# MI0283QT_v20.net
KiCad netlist of a schematic drawn in EAGLE
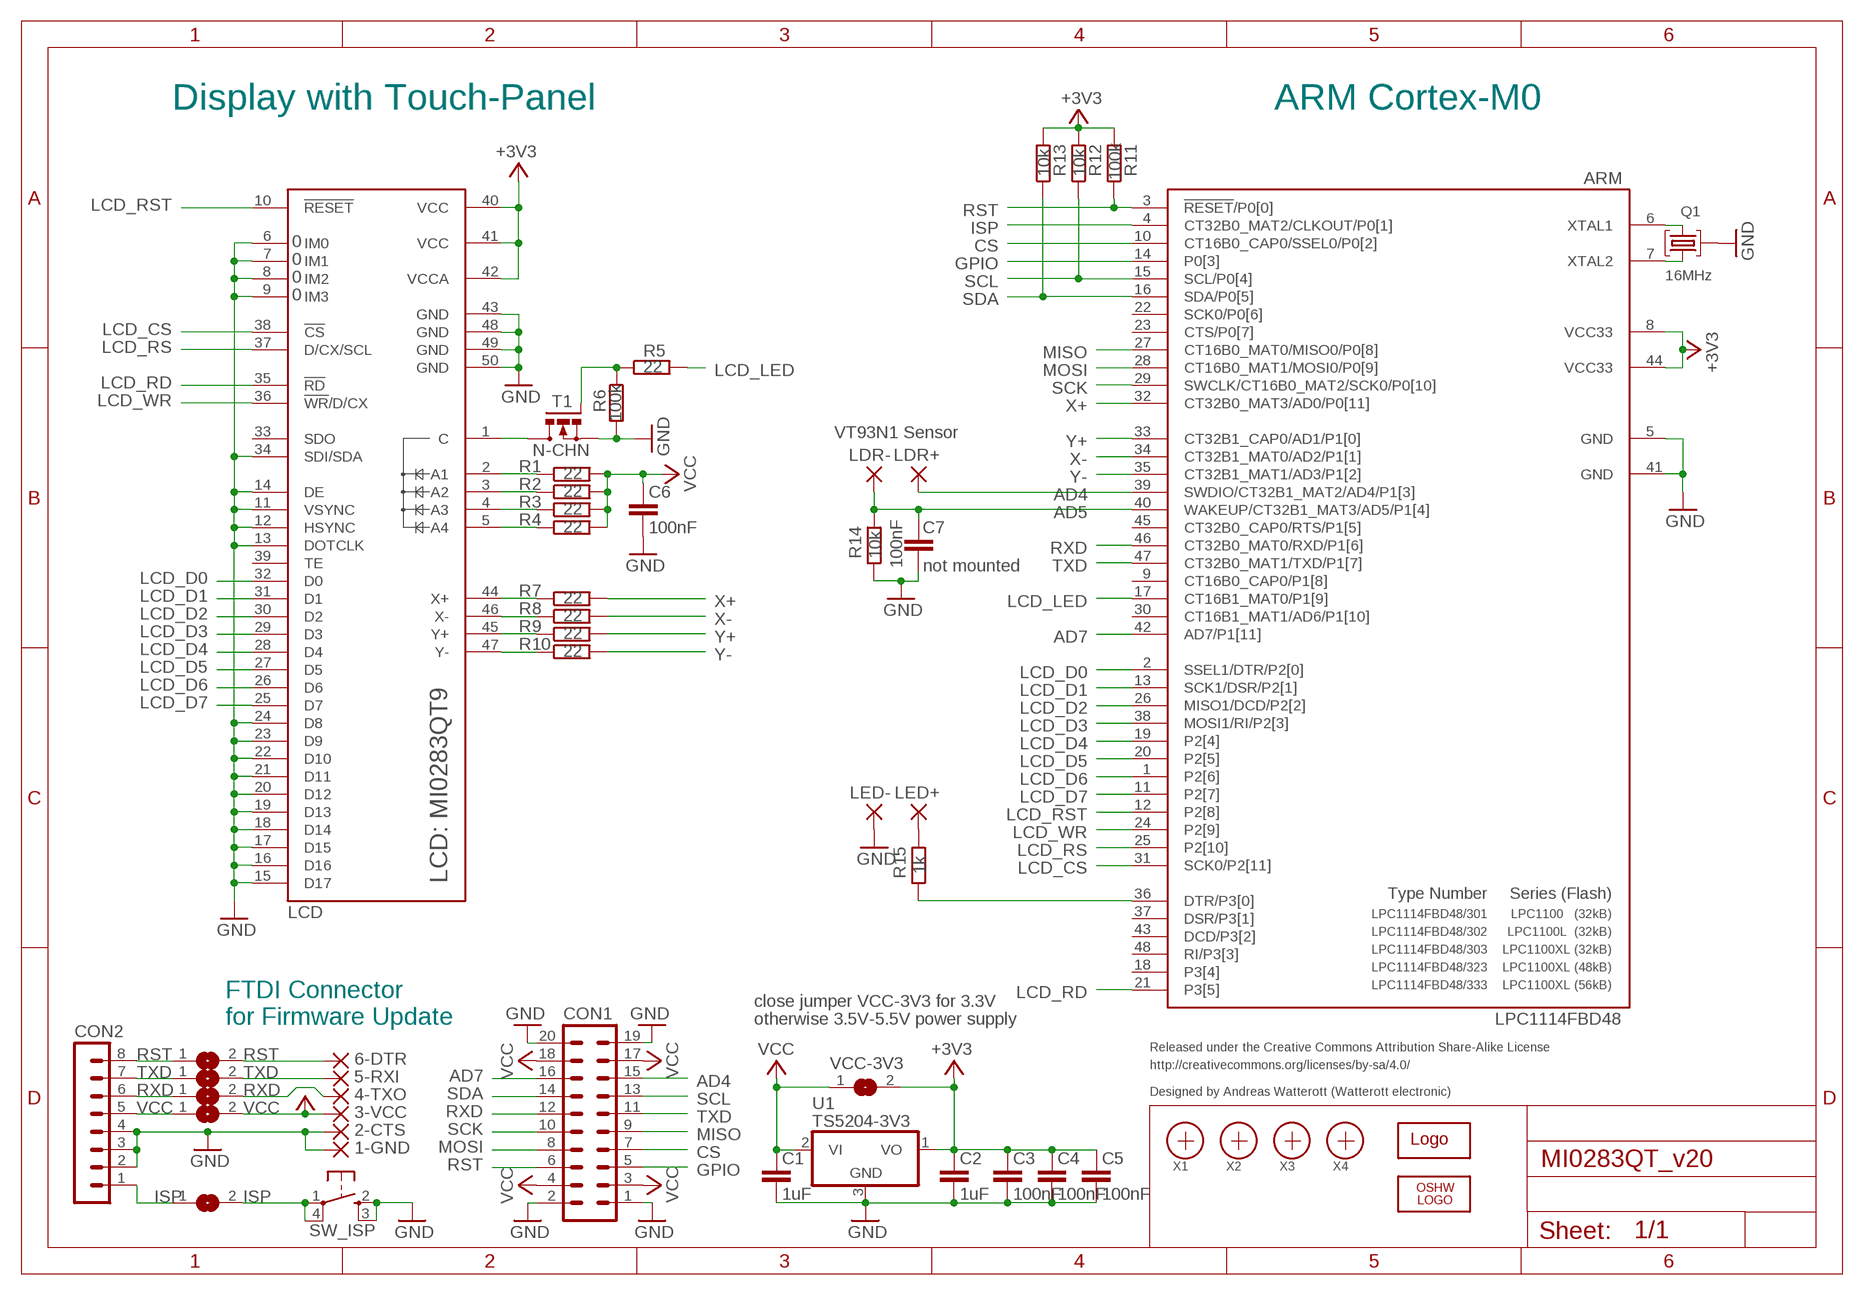
[diagram p0: schematic, sheet 1]

(export (version "E")
  (design (tool "Eeschema 10.0.6"))
  (components
    (comp (ref "1-GND")
      (value "WIREPADSMD1,27-254")
      (footprint "eagle-import:SMD1,27-2,54")
      (libsource (lib "eagle-import") (part "WIREPADSMD1,27-254"))
    )
    (comp (ref "2-CTS")
      (value "WIREPADSMD1,27-254")
      (footprint "eagle-import:SMD1,27-2,54")
      (libsource (lib "eagle-import") (part "WIREPADSMD1,27-254"))
    )
    (comp (ref "3-VCC")
      (value "WIREPADSMD1,27-254")
      (footprint "eagle-import:SMD1,27-2,54")
      (libsource (lib "eagle-import") (part "WIREPADSMD1,27-254"))
    )
    (comp (ref "4-TXO")
      (value "WIREPADSMD1,27-254")
      (footprint "eagle-import:SMD1,27-2,54")
      (libsource (lib "eagle-import") (part "WIREPADSMD1,27-254"))
    )
    (comp (ref "5-RXI")
      (value "WIREPADSMD1,27-254")
      (footprint "eagle-import:SMD1,27-2,54")
      (libsource (lib "eagle-import") (part "WIREPADSMD1,27-254"))
    )
    (comp (ref "6-DTR")
      (value "WIREPADSMD1,27-254")
      (footprint "eagle-import:SMD1,27-2,54")
      (libsource (lib "eagle-import") (part "WIREPADSMD1,27-254"))
    )
    (comp (ref "ARM")
      (value "LPC1114FBD48")
      (footprint "eagle-import:LQFP48")
      (libsource (lib "eagle-import") (part "LPC111X"))
    )
    (comp (ref "C1")
      (value "1uF")
      (footprint "eagle-import:C0603")
      (libsource (lib "eagle-import") (part "C-EUC0603"))
    )
    (comp (ref "C2")
      (value "1uF")
      (footprint "eagle-import:C0603")
      (libsource (lib "eagle-import") (part "C-EUC0603"))
    )
    (comp (ref "C3")
      (value "100nF")
      (footprint "eagle-import:C0603")
      (libsource (lib "eagle-import") (part "C-EUC0603"))
    )
    (comp (ref "C4")
      (value "100nF")
      (footprint "eagle-import:C0603")
      (libsource (lib "eagle-import") (part "C-EUC0603"))
    )
    (comp (ref "C5")
      (value "100nF")
      (footprint "eagle-import:C0603")
      (libsource (lib "eagle-import") (part "C-EUC0603"))
    )
    (comp (ref "C6")
      (value "100nF")
      (footprint "eagle-import:C0603")
      (libsource (lib "eagle-import") (part "C-EUC0603"))
    )
    (comp (ref "C7")
      (value "100nF")
      (footprint "eagle-import:C0603")
      (libsource (lib "eagle-import") (part "C-EUC0603"))
    )
    (comp (ref "CON1")
      (value "MA10-2")
      (footprint "eagle-import:MA10-2")
      (libsource (lib "eagle-import") (part "MA10-2"))
    )
    (comp (ref "CON2")
      (value "MA08-1")
      (footprint "eagle-import:MA08-1")
      (libsource (lib "eagle-import") (part "MA08-1"))
    )
    (comp (ref "ISP") (value "SJ") (footprint "eagle-import:SJ") (libsource (lib "eagle-import") (part "SJ")))
    (comp (ref "LCD")
      (value "MI0283QT9")
      (footprint "eagle-import:MI0283QT9")
      (libsource (lib "eagle-import") (part "MI0283QT9"))
    )
    (comp (ref "LDR+")
      (value "WIREPAD2,15/1,0")
      (footprint "eagle-import:2,15_1,0")
      (libsource (lib "eagle-import") (part "WIREPAD2,15/1,0"))
    )
    (comp (ref "LDR-")
      (value "WIREPAD2,15/1,0")
      (footprint "eagle-import:2,15_1,0")
      (libsource (lib "eagle-import") (part "WIREPAD2,15/1,0"))
    )
    (comp (ref "LED+")
      (value "WIREPAD2,15/1,0")
      (footprint "eagle-import:2,15_1,0")
      (libsource (lib "eagle-import") (part "WIREPAD2,15/1,0"))
    )
    (comp (ref "LED-")
      (value "WIREPAD2,15/1,0")
      (footprint "eagle-import:2,15_1,0")
      (libsource (lib "eagle-import") (part "WIREPAD2,15/1,0"))
    )
    (comp (ref "LOGO1")
      (value "OSHW_LOGO_6MILX0150-NT")
      (footprint "eagle-import:OSHW_6X150_NOTEXT")
      (libsource (lib "eagle-import") (part "OSHW_LOGO_6MILX0150-NT"))
    )
    (comp (ref "Q1")
      (value "16MHz")
      (footprint "eagle-import:SMD_OSC_35X15")
      (libsource (lib "eagle-import") (part "SMD_OSC2"))
    )
    (comp (ref "R1")
      (value "22")
      (footprint "eagle-import:R0603")
      (libsource (lib "eagle-import") (part "R-EU_R0603"))
    )
    (comp (ref "R2")
      (value "22")
      (footprint "eagle-import:R0603")
      (libsource (lib "eagle-import") (part "R-EU_R0603"))
    )
    (comp (ref "R3")
      (value "22")
      (footprint "eagle-import:R0603")
      (libsource (lib "eagle-import") (part "R-EU_R0603"))
    )
    (comp (ref "R4")
      (value "22")
      (footprint "eagle-import:R0603")
      (libsource (lib "eagle-import") (part "R-EU_R0603"))
    )
    (comp (ref "R5")
      (value "22")
      (footprint "eagle-import:R0603")
      (libsource (lib "eagle-import") (part "R-EU_R0603"))
    )
    (comp (ref "R6")
      (value "100k")
      (footprint "eagle-import:R0603")
      (libsource (lib "eagle-import") (part "R-EU_R0603"))
    )
    (comp (ref "R7")
      (value "22")
      (footprint "eagle-import:R0603")
      (libsource (lib "eagle-import") (part "R-EU_R0603"))
    )
    (comp (ref "R8")
      (value "22")
      (footprint "eagle-import:R0603")
      (libsource (lib "eagle-import") (part "R-EU_R0603"))
    )
    (comp (ref "R9")
      (value "22")
      (footprint "eagle-import:R0603")
      (libsource (lib "eagle-import") (part "R-EU_R0603"))
    )
    (comp (ref "R10")
      (value "22")
      (footprint "eagle-import:R0603")
      (libsource (lib "eagle-import") (part "R-EU_R0603"))
    )
    (comp (ref "R11")
      (value "100k")
      (footprint "eagle-import:R0603")
      (libsource (lib "eagle-import") (part "R-EU_R0603"))
    )
    (comp (ref "R12")
      (value "10k")
      (footprint "eagle-import:R0603")
      (libsource (lib "eagle-import") (part "R-EU_R0603"))
    )
    (comp (ref "R13")
      (value "10k")
      (footprint "eagle-import:R0603")
      (libsource (lib "eagle-import") (part "R-EU_R0603"))
    )
    (comp (ref "R14")
      (value "10k")
      (footprint "eagle-import:R0603")
      (libsource (lib "eagle-import") (part "R-EU_R0603"))
    )
    (comp (ref "R15")
      (value "1k")
      (footprint "eagle-import:R0603")
      (libsource (lib "eagle-import") (part "R-EU_R0603"))
    )
    (comp (ref "RST") (value "SJ") (footprint "eagle-import:SJ") (libsource (lib "eagle-import") (part "SJ")))
    (comp (ref "RXD") (value "SJ") (footprint "eagle-import:SJ") (libsource (lib "eagle-import") (part "SJ")))
    (comp (ref "SW_ISP")
      (value "SW_SMDS")
      (footprint "eagle-import:SW_SMD4@1")
      (libsource (lib "eagle-import") (part "SW_SMDS"))
    )
    (comp (ref "T1")
      (value "N-CHN")
      (footprint "eagle-import:MICRO3")
      (libsource (lib "eagle-import") (part "IRLML2502"))
    )
    (comp (ref "TXD") (value "SJ") (footprint "eagle-import:SJ") (libsource (lib "eagle-import") (part "SJ")))
    (comp (ref "U$1")
      (value "WE-LOGO")
      (footprint "eagle-import:WE-LOGO")
      (libsource (lib "eagle-import") (part "WE-LOGOPLACE"))
    )
    (comp (ref "U1")
      (value "TS5204-3V3")
      (footprint "eagle-import:SOT23")
      (libsource (lib "eagle-import") (part "TS5204"))
    )
    (comp (ref "VCC") (value "SJ") (footprint "eagle-import:SJ") (libsource (lib "eagle-import") (part "SJ")))
    (comp (ref "VCC-3V3")
      (value "SJ")
      (footprint "eagle-import:SJ")
      (libsource (lib "eagle-import") (part "SJ"))
    )
    (comp (ref "X1")
      (value "PASSER")
      (footprint "eagle-import:PASSER")
      (libsource (lib "eagle-import") (part "PASSER"))
    )
    (comp (ref "X2")
      (value "PASSER")
      (footprint "eagle-import:PASSER")
      (libsource (lib "eagle-import") (part "PASSER"))
    )
    (comp (ref "X3")
      (value "PASSER")
      (footprint "eagle-import:PASSER")
      (libsource (lib "eagle-import") (part "PASSER"))
    )
    (comp (ref "X4")
      (value "PASSER")
      (footprint "eagle-import:PASSER")
      (libsource (lib "eagle-import") (part "PASSER"))
    )
  )
  (nets
    (net (code "1") (name "+3V3") (class "Default")
      (node (ref "ARM") (pin "44") (pinfunction "VCC33_44") (pintype "bidirectional"))
      (node (ref "ARM") (pin "8") (pinfunction "VCC33_8") (pintype "bidirectional"))
      (node (ref "C2") (pin "1") (pinfunction "1_1") (pintype "passive"))
      (node (ref "C3") (pin "1") (pinfunction "1_1") (pintype "passive"))
      (node (ref "C4") (pin "1") (pinfunction "1_1") (pintype "passive"))
      (node (ref "C5") (pin "1") (pinfunction "1_1") (pintype "passive"))
      (node (ref "LCD") (pin "40") (pinfunction "VCC_40") (pintype "power_in"))
      (node (ref "LCD") (pin "41") (pinfunction "VCC_41") (pintype "power_in"))
      (node (ref "LCD") (pin "42") (pinfunction "VCCA_42") (pintype "power_in"))
      (node (ref "R11") (pin "2") (pinfunction "2_2") (pintype "passive"))
      (node (ref "R12") (pin "2") (pinfunction "2_2") (pintype "passive"))
      (node (ref "R13") (pin "2") (pinfunction "2_2") (pintype "passive"))
      (node (ref "U1") (pin "1") (pinfunction "VO_1") (pintype "passive"))
      (node (ref "VCC-3V3") (pin "2") (pinfunction "2_2") (pintype "passive"))
    )
    (net (code "2") (name "/AD4") (class "Default")
      (node (ref "ARM") (pin "39") (pinfunction "SWDIO/CT32B1_MAT2/AD4/P1[3]_39") (pintype "bidirectional"))
      (node (ref "CON1") (pin "15") (pinfunction "15_15") (pintype "passive"))
      (node (ref "LDR+") (pin "1") (pinfunction "P_1") (pintype "passive"))
    )
    (net (code "3") (name "/AD5") (class "Default")
      (node (ref "ARM") (pin "40") (pinfunction "WAKEUP/CT32B1_MAT3/AD5/P1[4]_40") (pintype "bidirectional"))
      (node (ref "C7") (pin "1") (pinfunction "1_1") (pintype "passive"))
      (node (ref "LDR-") (pin "1") (pinfunction "P_1") (pintype "passive"))
      (node (ref "R14") (pin "2") (pinfunction "2_2") (pintype "passive"))
    )
    (net (code "4") (name "/AD7") (class "Default")
      (node (ref "ARM") (pin "42") (pinfunction "AD7/P1[11]_42") (pintype "bidirectional"))
      (node (ref "CON1") (pin "16") (pinfunction "16_16") (pintype "passive"))
    )
    (net (code "5") (name "/CS") (class "Default")
      (node (ref "ARM") (pin "10") (pinfunction "CT16B0_CAP0/SSEL0/P0[2]_10") (pintype "bidirectional"))
      (node (ref "CON1") (pin "7") (pinfunction "7_7") (pintype "passive"))
    )
    (net (code "6") (name "/GPIO") (class "Default")
      (node (ref "ARM") (pin "14") (pinfunction "P0[3]_14") (pintype "bidirectional"))
      (node (ref "CON1") (pin "5") (pinfunction "5_5") (pintype "passive"))
    )
    (net (code "7") (name "/ISP") (class "Default")
      (node (ref "ARM") (pin "4") (pinfunction "CT32B0_MAT2/CLKOUT/P0[1]_4") (pintype "bidirectional"))
      (node (ref "ISP") (pin "2") (pinfunction "2_2") (pintype "passive"))
      (node (ref "SW_ISP") (pin "1") (pinfunction "P_1") (pintype "passive"))
      (node (ref "SW_ISP") (pin "4") (pinfunction "P1_4") (pintype "passive"))
    )
    (net (code "8") (name "/LCD_CS") (class "Default")
      (node (ref "ARM") (pin "31") (pinfunction "SCK0/P2[11]_31") (pintype "bidirectional"))
      (node (ref "LCD") (pin "38") (pinfunction "~{CS}_38") (pintype "input"))
    )
    (net (code "9") (name "/LCD_D0") (class "Default")
      (node (ref "ARM") (pin "2") (pinfunction "SSEL1/DTR/P2[0]_2") (pintype "bidirectional"))
      (node (ref "LCD") (pin "32") (pinfunction "D0_32") (pintype "input"))
    )
    (net (code "10") (name "/LCD_D1") (class "Default")
      (node (ref "ARM") (pin "13") (pinfunction "SCK1/DSR/P2[1]_13") (pintype "bidirectional"))
      (node (ref "LCD") (pin "31") (pinfunction "D1_31") (pintype "input"))
    )
    (net (code "11") (name "/LCD_D2") (class "Default")
      (node (ref "ARM") (pin "26") (pinfunction "MISO1/DCD/P2[2]_26") (pintype "bidirectional"))
      (node (ref "LCD") (pin "30") (pinfunction "D2_30") (pintype "input"))
    )
    (net (code "12") (name "/LCD_D3") (class "Default")
      (node (ref "ARM") (pin "38") (pinfunction "MOSI1/RI/P2[3]_38") (pintype "bidirectional"))
      (node (ref "LCD") (pin "29") (pinfunction "D3_29") (pintype "input"))
    )
    (net (code "13") (name "/LCD_D4") (class "Default")
      (node (ref "ARM") (pin "19") (pinfunction "P2[4]_19") (pintype "bidirectional"))
      (node (ref "LCD") (pin "28") (pinfunction "D4_28") (pintype "input"))
    )
    (net (code "14") (name "/LCD_D5") (class "Default")
      (node (ref "ARM") (pin "20") (pinfunction "P2[5]_20") (pintype "bidirectional"))
      (node (ref "LCD") (pin "27") (pinfunction "D5_27") (pintype "input"))
    )
    (net (code "15") (name "/LCD_D6") (class "Default")
      (node (ref "ARM") (pin "1") (pinfunction "P2[6]_1") (pintype "bidirectional"))
      (node (ref "LCD") (pin "26") (pinfunction "D6_26") (pintype "input"))
    )
    (net (code "16") (name "/LCD_D7") (class "Default")
      (node (ref "ARM") (pin "11") (pinfunction "P2[7]_11") (pintype "bidirectional"))
      (node (ref "LCD") (pin "25") (pinfunction "D7_25") (pintype "input"))
    )
    (net (code "17") (name "/LCD_LED") (class "Default")
      (node (ref "ARM") (pin "17") (pinfunction "CT16B1_MAT0/P1[9]_17") (pintype "bidirectional"))
      (node (ref "R5") (pin "2") (pinfunction "2_2") (pintype "passive"))
    )
    (net (code "18") (name "/LCD_RD") (class "Default")
      (node (ref "ARM") (pin "21") (pinfunction "P3[5]_21") (pintype "bidirectional"))
      (node (ref "LCD") (pin "35") (pinfunction "~{RD}_35") (pintype "input"))
    )
    (net (code "19") (name "/LCD_RS") (class "Default")
      (node (ref "ARM") (pin "25") (pinfunction "P2[10]_25") (pintype "bidirectional"))
      (node (ref "LCD") (pin "37") (pinfunction "D/CX/SCL_37") (pintype "input"))
    )
    (net (code "20") (name "/LCD_RST") (class "Default")
      (node (ref "ARM") (pin "12") (pinfunction "P2[8]_12") (pintype "bidirectional"))
      (node (ref "LCD") (pin "10") (pinfunction "~{RESET}_10") (pintype "input"))
    )
    (net (code "21") (name "/LCD_WR") (class "Default")
      (node (ref "ARM") (pin "24") (pinfunction "P2[9]_24") (pintype "bidirectional"))
      (node (ref "LCD") (pin "36") (pinfunction "~{WR}/D/CX_36") (pintype "input"))
    )
    (net (code "22") (name "/MISO") (class "Default")
      (node (ref "ARM") (pin "27") (pinfunction "CT16B0_MAT0/MISO0/P0[8]_27") (pintype "bidirectional"))
      (node (ref "CON1") (pin "9") (pinfunction "9_9") (pintype "passive"))
    )
    (net (code "23") (name "/MOSI") (class "Default")
      (node (ref "ARM") (pin "28") (pinfunction "CT16B0_MAT1/MOSI0/P0[9]_28") (pintype "bidirectional"))
      (node (ref "CON1") (pin "8") (pinfunction "8_8") (pintype "passive"))
    )
    (net (code "24") (name "/RST") (class "Default")
      (node (ref "6-DTR") (pin "1") (pinfunction "P_1") (pintype "passive"))
      (node (ref "ARM") (pin "3") (pinfunction "~{RESET}/P0[0]_3") (pintype "bidirectional"))
      (node (ref "CON1") (pin "6") (pinfunction "6_6") (pintype "passive"))
      (node (ref "R11") (pin "1") (pinfunction "1_1") (pintype "passive"))
      (node (ref "RST") (pin "2") (pinfunction "2_2") (pintype "passive"))
    )
    (net (code "25") (name "/RXD") (class "Default")
      (node (ref "4-TXO") (pin "1") (pinfunction "P_1") (pintype "passive"))
      (node (ref "ARM") (pin "46") (pinfunction "CT32B0_MAT0/RXD/P1[6]_46") (pintype "bidirectional"))
      (node (ref "CON1") (pin "12") (pinfunction "12_12") (pintype "passive"))
      (node (ref "RXD") (pin "2") (pinfunction "2_2") (pintype "passive"))
    )
    (net (code "26") (name "/SCK") (class "Default")
      (node (ref "ARM") (pin "29") (pinfunction "SWCLK/CT16B0_MAT2/SCK0/P0[10]_29") (pintype "bidirectional"))
      (node (ref "CON1") (pin "10") (pinfunction "10_10") (pintype "passive"))
    )
    (net (code "27") (name "/SCL") (class "Default")
      (node (ref "ARM") (pin "15") (pinfunction "SCL/P0[4]_15") (pintype "bidirectional"))
      (node (ref "CON1") (pin "13") (pinfunction "13_13") (pintype "passive"))
      (node (ref "R12") (pin "1") (pinfunction "1_1") (pintype "passive"))
    )
    (net (code "28") (name "/SDA") (class "Default")
      (node (ref "ARM") (pin "16") (pinfunction "SDA/P0[5]_16") (pintype "bidirectional"))
      (node (ref "CON1") (pin "14") (pinfunction "14_14") (pintype "passive"))
      (node (ref "R13") (pin "1") (pinfunction "1_1") (pintype "passive"))
    )
    (net (code "29") (name "/TXD") (class "Default")
      (node (ref "5-RXI") (pin "1") (pinfunction "P_1") (pintype "passive"))
      (node (ref "ARM") (pin "47") (pinfunction "CT32B0_MAT1/TXD/P1[7]_47") (pintype "bidirectional"))
      (node (ref "CON1") (pin "11") (pinfunction "11_11") (pintype "passive"))
      (node (ref "TXD") (pin "2") (pinfunction "2_2") (pintype "passive"))
    )
    (net (code "30") (name "/X+") (class "Default")
      (node (ref "ARM") (pin "32") (pinfunction "CT32B0_MAT3/AD0/P0[11]_32") (pintype "bidirectional"))
      (node (ref "R7") (pin "2") (pinfunction "2_2") (pintype "passive"))
    )
    (net (code "31") (name "/X-") (class "Default")
      (node (ref "ARM") (pin "34") (pinfunction "CT32B1_MAT0/AD2/P1[1]_34") (pintype "bidirectional"))
      (node (ref "R8") (pin "2") (pinfunction "2_2") (pintype "passive"))
    )
    (net (code "32") (name "/Y+") (class "Default")
      (node (ref "ARM") (pin "33") (pinfunction "CT32B1_CAP0/AD1/P1[0]_33") (pintype "bidirectional"))
      (node (ref "R9") (pin "2") (pinfunction "2_2") (pintype "passive"))
    )
    (net (code "33") (name "/Y-") (class "Default")
      (node (ref "ARM") (pin "35") (pinfunction "CT32B1_MAT1/AD3/P1[2]_35") (pintype "bidirectional"))
      (node (ref "R10") (pin "2") (pinfunction "2_2") (pintype "passive"))
    )
    (net (code "34") (name "GND") (class "Default")
      (node (ref "1-GND") (pin "1") (pinfunction "P_1") (pintype "passive"))
      (node (ref "2-CTS") (pin "1") (pinfunction "P_1") (pintype "passive"))
      (node (ref "ARM") (pin "41") (pinfunction "GND_41") (pintype "bidirectional"))
      (node (ref "ARM") (pin "5") (pinfunction "GND_5") (pintype "bidirectional"))
      (node (ref "C1") (pin "2") (pinfunction "2_2") (pintype "passive"))
      (node (ref "C2") (pin "2") (pinfunction "2_2") (pintype "passive"))
      (node (ref "C3") (pin "2") (pinfunction "2_2") (pintype "passive"))
      (node (ref "C4") (pin "2") (pinfunction "2_2") (pintype "passive"))
      (node (ref "C5") (pin "2") (pinfunction "2_2") (pintype "passive"))
      (node (ref "C6") (pin "2") (pinfunction "2_2") (pintype "passive"))
      (node (ref "C7") (pin "2") (pinfunction "2_2") (pintype "passive"))
      (node (ref "CON1") (pin "1") (pinfunction "1_1") (pintype "passive"))
      (node (ref "CON1") (pin "19") (pinfunction "19_19") (pintype "passive"))
      (node (ref "CON1") (pin "2") (pinfunction "2_2") (pintype "passive"))
      (node (ref "CON1") (pin "20") (pinfunction "20_20") (pintype "passive"))
      (node (ref "CON2") (pin "2") (pinfunction "2_2") (pintype "passive"))
      (node (ref "CON2") (pin "3") (pinfunction "3_3") (pintype "passive"))
      (node (ref "CON2") (pin "4") (pinfunction "4_4") (pintype "passive"))
      (node (ref "LCD") (pin "11") (pinfunction "VSYNC_11") (pintype "input"))
      (node (ref "LCD") (pin "12") (pinfunction "HSYNC_12") (pintype "input"))
      (node (ref "LCD") (pin "13") (pinfunction "DOTCLK_13") (pintype "input"))
      (node (ref "LCD") (pin "14") (pinfunction "DE_14") (pintype "input"))
      (node (ref "LCD") (pin "15") (pinfunction "D17_15") (pintype "input"))
      (node (ref "LCD") (pin "16") (pinfunction "D16_16") (pintype "input"))
      (node (ref "LCD") (pin "17") (pinfunction "D15_17") (pintype "input"))
      (node (ref "LCD") (pin "18") (pinfunction "D14_18") (pintype "input"))
      (node (ref "LCD") (pin "19") (pinfunction "D13_19") (pintype "input"))
      (node (ref "LCD") (pin "20") (pinfunction "D12_20") (pintype "input"))
      (node (ref "LCD") (pin "21") (pinfunction "D11_21") (pintype "input"))
      (node (ref "LCD") (pin "22") (pinfunction "D10_22") (pintype "input"))
      (node (ref "LCD") (pin "23") (pinfunction "D9_23") (pintype "input"))
      (node (ref "LCD") (pin "24") (pinfunction "D8_24") (pintype "input"))
      (node (ref "LCD") (pin "34") (pinfunction "SDI/SDA_34") (pintype "input"))
      (node (ref "LCD") (pin "43") (pinfunction "GND_43") (pintype "power_in"))
      (node (ref "LCD") (pin "48") (pinfunction "GND_48") (pintype "power_in"))
      (node (ref "LCD") (pin "49") (pinfunction "GND_49") (pintype "power_in"))
      (node (ref "LCD") (pin "50") (pinfunction "GND_50") (pintype "power_in"))
      (node (ref "LCD") (pin "6") (pinfunction "IM0_6") (pintype "input"))
      (node (ref "LCD") (pin "7") (pinfunction "IM1_7") (pintype "input"))
      (node (ref "LCD") (pin "8") (pinfunction "IM2_8") (pintype "input"))
      (node (ref "LCD") (pin "9") (pinfunction "IM3_9") (pintype "input"))
      (node (ref "LED-") (pin "1") (pinfunction "P_1") (pintype "passive"))
      (node (ref "Q1") (pin "GND") (pinfunction "GND_GND") (pintype "passive"))
      (node (ref "R14") (pin "1") (pinfunction "1_1") (pintype "passive"))
      (node (ref "R6") (pin "2") (pinfunction "2_2") (pintype "passive"))
      (node (ref "SW_ISP") (pin "2") (pinfunction "S_2") (pintype "passive"))
      (node (ref "SW_ISP") (pin "3") (pinfunction "S1_3") (pintype "passive"))
      (node (ref "T1") (pin "2") (pinfunction "S_2") (pintype "passive"))
      (node (ref "U1") (pin "3") (pinfunction "GND_3") (pintype "passive"))
    )
    (net (code "35") (name "Net-(ARM-DTR{slash}P3[0])") (class "Default")
      (node (ref "ARM") (pin "36") (pinfunction "DTR/P3[0]_36") (pintype "bidirectional"))
      (node (ref "R15") (pin "1") (pinfunction "1_1") (pintype "passive"))
    )
    (net (code "36") (name "Net-(ARM-XTAL1)") (class "Default")
      (node (ref "ARM") (pin "6") (pinfunction "XTAL1_6") (pintype "bidirectional"))
      (node (ref "Q1") (pin "2") (pinfunction "2_2") (pintype "passive"))
    )
    (net (code "37") (name "Net-(ARM-XTAL2)") (class "Default")
      (node (ref "ARM") (pin "7") (pinfunction "XTAL2_7") (pintype "bidirectional"))
      (node (ref "Q1") (pin "1") (pinfunction "1_1") (pintype "passive"))
    )
    (net (code "38") (name "Net-(CON2-Pad1)") (class "Default")
      (node (ref "CON2") (pin "1") (pinfunction "1_1") (pintype "passive"))
      (node (ref "ISP") (pin "1") (pinfunction "1_1") (pintype "passive"))
    )
    (net (code "39") (name "Net-(CON2-Pad5)") (class "Default")
      (node (ref "CON2") (pin "5") (pinfunction "5_5") (pintype "passive"))
      (node (ref "VCC") (pin "1") (pinfunction "1_1") (pintype "passive"))
    )
    (net (code "40") (name "Net-(CON2-Pad6)") (class "Default")
      (node (ref "CON2") (pin "6") (pinfunction "6_6") (pintype "passive"))
      (node (ref "RXD") (pin "1") (pinfunction "1_1") (pintype "passive"))
    )
    (net (code "41") (name "Net-(CON2-Pad7)") (class "Default")
      (node (ref "CON2") (pin "7") (pinfunction "7_7") (pintype "passive"))
      (node (ref "TXD") (pin "1") (pinfunction "1_1") (pintype "passive"))
    )
    (net (code "42") (name "Net-(CON2-Pad8)") (class "Default")
      (node (ref "CON2") (pin "8") (pinfunction "8_8") (pintype "passive"))
      (node (ref "RST") (pin "1") (pinfunction "1_1") (pintype "passive"))
    )
    (net (code "43") (name "Net-(LCD-A1)") (class "Default")
      (node (ref "LCD") (pin "2") (pinfunction "A1_2") (pintype "power_in"))
      (node (ref "R1") (pin "1") (pinfunction "1_1") (pintype "passive"))
    )
    (net (code "44") (name "Net-(LCD-A2)") (class "Default")
      (node (ref "LCD") (pin "3") (pinfunction "A2_3") (pintype "power_in"))
      (node (ref "R2") (pin "1") (pinfunction "1_1") (pintype "passive"))
    )
    (net (code "45") (name "Net-(LCD-A3)") (class "Default")
      (node (ref "LCD") (pin "4") (pinfunction "A3_4") (pintype "power_in"))
      (node (ref "R3") (pin "1") (pinfunction "1_1") (pintype "passive"))
    )
    (net (code "46") (name "Net-(LCD-A4)") (class "Default")
      (node (ref "LCD") (pin "5") (pinfunction "A4_5") (pintype "power_in"))
      (node (ref "R4") (pin "1") (pinfunction "1_1") (pintype "passive"))
    )
    (net (code "47") (name "Net-(LCD-C)") (class "Default")
      (node (ref "LCD") (pin "1") (pinfunction "C_1") (pintype "power_in"))
      (node (ref "T1") (pin "3") (pinfunction "D_3") (pintype "passive"))
    )
    (net (code "48") (name "Net-(LCD-X+)") (class "Default")
      (node (ref "LCD") (pin "44") (pinfunction "X+_44") (pintype "passive"))
      (node (ref "R7") (pin "1") (pinfunction "1_1") (pintype "passive"))
    )
    (net (code "49") (name "Net-(LCD-X-)") (class "Default")
      (node (ref "LCD") (pin "46") (pinfunction "X-_46") (pintype "passive"))
      (node (ref "R8") (pin "1") (pinfunction "1_1") (pintype "passive"))
    )
    (net (code "50") (name "Net-(LCD-Y+)") (class "Default")
      (node (ref "LCD") (pin "45") (pinfunction "Y+_45") (pintype "passive"))
      (node (ref "R9") (pin "1") (pinfunction "1_1") (pintype "passive"))
    )
    (net (code "51") (name "Net-(LCD-Y-)") (class "Default")
      (node (ref "LCD") (pin "47") (pinfunction "Y-_47") (pintype "passive"))
      (node (ref "R10") (pin "1") (pinfunction "1_1") (pintype "passive"))
    )
    (net (code "52") (name "Net-(LED+-P)") (class "Default")
      (node (ref "LED+") (pin "1") (pinfunction "P_1") (pintype "passive"))
      (node (ref "R15") (pin "2") (pinfunction "2_2") (pintype "passive"))
    )
    (net (code "53") (name "Net-(T1-G)") (class "Default")
      (node (ref "R5") (pin "1") (pinfunction "1_1") (pintype "passive"))
      (node (ref "R6") (pin "1") (pinfunction "1_1") (pintype "passive"))
      (node (ref "T1") (pin "1") (pinfunction "G_1") (pintype "passive"))
    )
    (net (code "54") (name "VCC") (class "Default")
      (node (ref "3-VCC") (pin "1") (pinfunction "P_1") (pintype "passive"))
      (node (ref "C1") (pin "1") (pinfunction "1_1") (pintype "passive"))
      (node (ref "C6") (pin "1") (pinfunction "1_1") (pintype "passive"))
      (node (ref "CON1") (pin "17") (pinfunction "17_17") (pintype "passive"))
      (node (ref "CON1") (pin "18") (pinfunction "18_18") (pintype "passive"))
      (node (ref "CON1") (pin "3") (pinfunction "3_3") (pintype "passive"))
      (node (ref "CON1") (pin "4") (pinfunction "4_4") (pintype "passive"))
      (node (ref "R1") (pin "2") (pinfunction "2_2") (pintype "passive"))
      (node (ref "R2") (pin "2") (pinfunction "2_2") (pintype "passive"))
      (node (ref "R3") (pin "2") (pinfunction "2_2") (pintype "passive"))
      (node (ref "R4") (pin "2") (pinfunction "2_2") (pintype "passive"))
      (node (ref "U1") (pin "2") (pinfunction "VI_2") (pintype "input"))
      (node (ref "VCC") (pin "2") (pinfunction "2_2") (pintype "passive"))
      (node (ref "VCC-3V3") (pin "1") (pinfunction "1_1") (pintype "passive"))
    )
    (net (code "55") (name "unconnected-(ARM-CT16B0_CAP0{slash}P1[8]-Pad9)") (class "Default")
      (node (ref "ARM") (pin "9") (pinfunction "CT16B0_CAP0/P1[8]_9") (pintype "bidirectional"))
    )
    (net (code "56") (name "unconnected-(ARM-CT16B1_MAT1{slash}AD6{slash}P1[10]-Pad30)") (class "Default")
      (node (ref "ARM") (pin "30") (pinfunction "CT16B1_MAT1/AD6/P1[10]_30") (pintype "bidirectional"))
    )
    (net (code "57") (name "unconnected-(ARM-CT32B0_CAP0{slash}RTS{slash}P1[5]-Pad45)") (class "Default")
      (node (ref "ARM") (pin "45") (pinfunction "CT32B0_CAP0/RTS/P1[5]_45") (pintype "bidirectional"))
    )
    (net (code "58") (name "unconnected-(ARM-CTS{slash}P0[7]-Pad23)") (class "Default")
      (node (ref "ARM") (pin "23") (pinfunction "CTS/P0[7]_23") (pintype "bidirectional"))
    )
    (net (code "59") (name "unconnected-(ARM-DCD{slash}P3[2]-Pad43)") (class "Default")
      (node (ref "ARM") (pin "43") (pinfunction "DCD/P3[2]_43") (pintype "bidirectional"))
    )
    (net (code "60") (name "unconnected-(ARM-DSR{slash}P3[1]-Pad37)") (class "Default")
      (node (ref "ARM") (pin "37") (pinfunction "DSR/P3[1]_37") (pintype "bidirectional"))
    )
    (net (code "61") (name "unconnected-(ARM-P3[4]-Pad18)") (class "Default")
      (node (ref "ARM") (pin "18") (pinfunction "P3[4]_18") (pintype "bidirectional"))
    )
    (net (code "62") (name "unconnected-(ARM-RI{slash}P3[3]-Pad48)") (class "Default")
      (node (ref "ARM") (pin "48") (pinfunction "RI/P3[3]_48") (pintype "bidirectional"))
    )
    (net (code "63") (name "unconnected-(ARM-SCK0{slash}P0[6]-Pad22)") (class "Default")
      (node (ref "ARM") (pin "22") (pinfunction "SCK0/P0[6]_22") (pintype "bidirectional"))
    )
    (net (code "64") (name "unconnected-(LCD-SDO-Pad33)") (class "Default")
      (node (ref "LCD") (pin "33") (pinfunction "SDO_33") (pintype "output"))
    )
    (net (code "65") (name "unconnected-(LCD-TE-Pad39)") (class "Default")
      (node (ref "LCD") (pin "39") (pinfunction "TE_39") (pintype "output"))
    )
  )
)
